# DaFunc.net
KiCad netlist of a schematic drawn in EAGLE
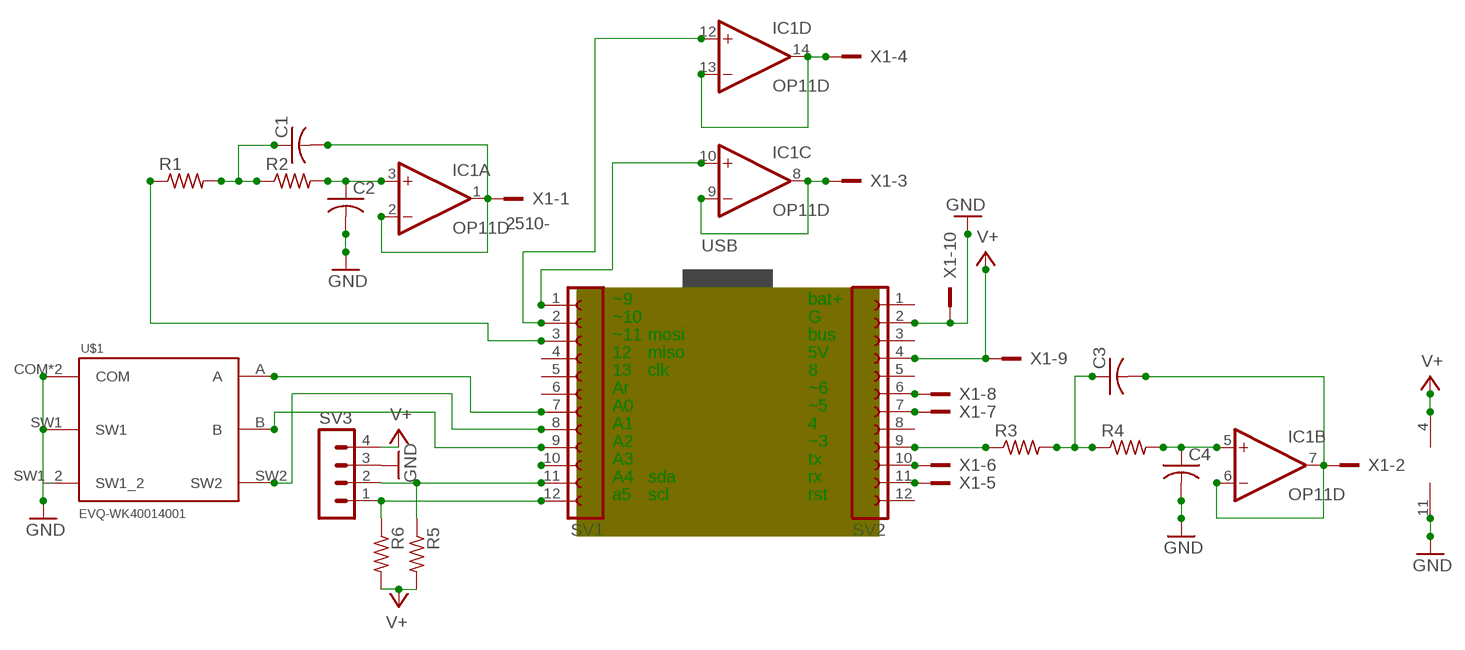
[diagram p0: schematic, sheet 1]

(export (version "E")
  (design (tool "Eeschema 10.0.6"))
  (components
    (comp (ref "C1")
      (value "C-USC0603")
      (footprint "eagle-import:C0603")
      (libsource (lib "eagle-import") (part "C-USC0603"))
    )
    (comp (ref "C2")
      (value "C-USC0603")
      (footprint "eagle-import:C0603")
      (libsource (lib "eagle-import") (part "C-USC0603"))
    )
    (comp (ref "C3")
      (value "C-USC0603")
      (footprint "eagle-import:C0603")
      (libsource (lib "eagle-import") (part "C-USC0603"))
    )
    (comp (ref "C4")
      (value "C-USC0603")
      (footprint "eagle-import:C0603")
      (libsource (lib "eagle-import") (part "C-USC0603"))
    )
    (comp (ref "IC1")
      (value "OP11D")
      (footprint "eagle-import:SO14")
      (libsource (lib "eagle-import") (part "OP11D"))
    )
    (comp (ref "R1")
      (value "R-US_R0603")
      (footprint "eagle-import:R0603")
      (libsource (lib "eagle-import") (part "R-US_R0603"))
    )
    (comp (ref "R2")
      (value "R-US_R0603")
      (footprint "eagle-import:R0603")
      (libsource (lib "eagle-import") (part "R-US_R0603"))
    )
    (comp (ref "R3")
      (value "R-US_R0603")
      (footprint "eagle-import:R0603")
      (libsource (lib "eagle-import") (part "R-US_R0603"))
    )
    (comp (ref "R4")
      (value "R-US_R0603")
      (footprint "eagle-import:R0603")
      (libsource (lib "eagle-import") (part "R-US_R0603"))
    )
    (comp (ref "R5")
      (value "R-US_R0603")
      (footprint "eagle-import:R0603")
      (libsource (lib "eagle-import") (part "R-US_R0603"))
    )
    (comp (ref "R6")
      (value "R-US_R0603")
      (footprint "eagle-import:R0603")
      (libsource (lib "eagle-import") (part "R-US_R0603"))
    )
    (comp (ref "SV1")
      (value "FE12-1")
      (footprint "eagle-import:FE12")
      (libsource (lib "eagle-import") (part "FE12-1"))
    )
    (comp (ref "SV2")
      (value "FE12-1")
      (footprint "eagle-import:FE12")
      (libsource (lib "eagle-import") (part "FE12-1"))
    )
    (comp (ref "SV3")
      (value "MA04-1")
      (footprint "eagle-import:MA04-1")
      (libsource (lib "eagle-import") (part "MA04-1"))
    )
    (comp (ref "U$1")
      (value "EVQ-WK40014001")
      (footprint "eagle-import:WK4")
      (libsource (lib "eagle-import") (part "EVQ-WK40014001"))
    )
    (comp (ref "X1")
      (value "2510-")
      (footprint "eagle-import:PAK100_2500-10")
      (fields (field (name "MF") "3M") (field (name "MPN") "2510-6002UB"))
      (libsource (lib "eagle-import") (part "2510-"))
    )
  )
  (nets
    (net (code "1") (name "GND") (class "Default")
      (node (ref "C2") (pin "2") (pinfunction "2_2") (pintype "passive"))
      (node (ref "C4") (pin "2") (pinfunction "2_2") (pintype "passive"))
      (node (ref "IC1") (pin "11") (pinfunction "V-_11") (pintype "power_in"))
      (node (ref "SV2") (pin "2") (pinfunction "2_2") (pintype "passive"))
      (node (ref "SV3") (pin "3") (pinfunction "3_3") (pintype "passive"))
      (node (ref "U$1") (pin "COM") (pinfunction "COM_COM") (pintype "bidirectional"))
      (node (ref "U$1") (pin "GND") (pinfunction "COM_GND") (pintype "bidirectional"))
      (node (ref "U$1") (pin "SW1") (pinfunction "SW1_SW1") (pintype "bidirectional"))
      (node (ref "U$1") (pin "SW1_2") (pinfunction "SW1_2_SW1_2") (pintype "bidirectional"))
      (node (ref "X1") (pin "10") (pinfunction "KL_10") (pintype "passive"))
    )
    (net (code "2") (name "Net-(C1-Pad1)") (class "Default")
      (node (ref "C1") (pin "1") (pinfunction "1_1") (pintype "passive"))
      (node (ref "R1") (pin "2") (pinfunction "2_2") (pintype "passive"))
      (node (ref "R2") (pin "1") (pinfunction "1_1") (pintype "passive"))
    )
    (net (code "3") (name "Net-(C3-Pad1)") (class "Default")
      (node (ref "C3") (pin "1") (pinfunction "1_1") (pintype "passive"))
      (node (ref "R3") (pin "2") (pinfunction "2_2") (pintype "passive"))
      (node (ref "R4") (pin "1") (pinfunction "1_1") (pintype "passive"))
    )
    (net (code "4") (name "Net-(IC1A-+IN)") (class "Default")
      (node (ref "C2") (pin "1") (pinfunction "1_1") (pintype "passive"))
      (node (ref "IC1") (pin "3") (pinfunction "+IN_3") (pintype "input"))
      (node (ref "R2") (pin "2") (pinfunction "2_2") (pintype "passive"))
    )
    (net (code "5") (name "Net-(IC1A--IN)") (class "Default")
      (node (ref "C1") (pin "2") (pinfunction "2_2") (pintype "passive"))
      (node (ref "IC1") (pin "1") (pinfunction "OUT_1") (pintype "output"))
      (node (ref "IC1") (pin "2") (pinfunction "-IN_2") (pintype "input"))
      (node (ref "X1") (pin "1") (pinfunction "KL_1") (pintype "passive"))
    )
    (net (code "6") (name "Net-(IC1B-+IN)") (class "Default")
      (node (ref "C4") (pin "1") (pinfunction "1_1") (pintype "passive"))
      (node (ref "IC1") (pin "5") (pinfunction "+IN_5") (pintype "input"))
      (node (ref "R4") (pin "2") (pinfunction "2_2") (pintype "passive"))
    )
    (net (code "7") (name "Net-(IC1B--IN)") (class "Default")
      (node (ref "C3") (pin "2") (pinfunction "2_2") (pintype "passive"))
      (node (ref "IC1") (pin "6") (pinfunction "-IN_6") (pintype "input"))
      (node (ref "IC1") (pin "7") (pinfunction "OUT_7") (pintype "output"))
      (node (ref "X1") (pin "2") (pinfunction "KL_2") (pintype "passive"))
    )
    (net (code "8") (name "Net-(IC1C-+IN)") (class "Default")
      (node (ref "IC1") (pin "10") (pinfunction "+IN_10") (pintype "input"))
      (node (ref "SV1") (pin "1") (pinfunction "1_1") (pintype "passive"))
    )
    (net (code "9") (name "Net-(IC1C--IN)") (class "Default")
      (node (ref "IC1") (pin "8") (pinfunction "OUT_8") (pintype "output"))
      (node (ref "IC1") (pin "9") (pinfunction "-IN_9") (pintype "input"))
      (node (ref "X1") (pin "3") (pinfunction "KL_3") (pintype "passive"))
    )
    (net (code "10") (name "Net-(IC1D-+IN)") (class "Default")
      (node (ref "IC1") (pin "12") (pinfunction "+IN_12") (pintype "input"))
      (node (ref "SV1") (pin "2") (pinfunction "2_2") (pintype "passive"))
    )
    (net (code "11") (name "Net-(IC1D--IN)") (class "Default")
      (node (ref "IC1") (pin "13") (pinfunction "-IN_13") (pintype "input"))
      (node (ref "IC1") (pin "14") (pinfunction "OUT_14") (pintype "output"))
      (node (ref "X1") (pin "4") (pinfunction "KL_4") (pintype "passive"))
    )
    (net (code "12") (name "Net-(R1-Pad1)") (class "Default")
      (node (ref "R1") (pin "1") (pinfunction "1_1") (pintype "passive"))
      (node (ref "SV1") (pin "3") (pinfunction "3_3") (pintype "passive"))
    )
    (net (code "13") (name "Net-(R3-Pad1)") (class "Default")
      (node (ref "R3") (pin "1") (pinfunction "1_1") (pintype "passive"))
      (node (ref "SV2") (pin "9") (pinfunction "9_9") (pintype "passive"))
    )
    (net (code "14") (name "Net-(R5-Pad1)") (class "Default")
      (node (ref "R5") (pin "1") (pinfunction "1_1") (pintype "passive"))
      (node (ref "SV1") (pin "11") (pinfunction "11_11") (pintype "passive"))
      (node (ref "SV3") (pin "2") (pinfunction "2_2") (pintype "passive"))
    )
    (net (code "15") (name "Net-(R6-Pad1)") (class "Default")
      (node (ref "R6") (pin "1") (pinfunction "1_1") (pintype "passive"))
      (node (ref "SV1") (pin "12") (pinfunction "12_12") (pintype "passive"))
      (node (ref "SV3") (pin "1") (pinfunction "1_1") (pintype "passive"))
    )
    (net (code "16") (name "Net-(SV1-Pad7)") (class "Default")
      (node (ref "SV1") (pin "7") (pinfunction "7_7") (pintype "passive"))
      (node (ref "U$1") (pin "A") (pinfunction "A_A") (pintype "bidirectional"))
    )
    (net (code "17") (name "Net-(SV1-Pad8)") (class "Default")
      (node (ref "SV1") (pin "8") (pinfunction "8_8") (pintype "passive"))
      (node (ref "U$1") (pin "SW2") (pinfunction "SW2_SW2") (pintype "bidirectional"))
    )
    (net (code "18") (name "Net-(SV1-Pad9)") (class "Default")
      (node (ref "SV1") (pin "9") (pinfunction "9_9") (pintype "passive"))
      (node (ref "U$1") (pin "B") (pinfunction "B_B") (pintype "bidirectional"))
    )
    (net (code "19") (name "Net-(X1F-KL)") (class "Default")
      (node (ref "SV2") (pin "11") (pinfunction "11_11") (pintype "passive"))
      (node (ref "X1") (pin "5") (pinfunction "KL_5") (pintype "passive"))
    )
    (net (code "20") (name "Net-(X1G-KL)") (class "Default")
      (node (ref "SV2") (pin "10") (pinfunction "10_10") (pintype "passive"))
      (node (ref "X1") (pin "6") (pinfunction "KL_6") (pintype "passive"))
    )
    (net (code "21") (name "Net-(X1H-KL)") (class "Default")
      (node (ref "SV2") (pin "7") (pinfunction "7_7") (pintype "passive"))
      (node (ref "X1") (pin "7") (pinfunction "KL_7") (pintype "passive"))
    )
    (net (code "22") (name "Net-(X1I-KL)") (class "Default")
      (node (ref "SV2") (pin "6") (pinfunction "6_6") (pintype "passive"))
      (node (ref "X1") (pin "8") (pinfunction "KL_8") (pintype "passive"))
    )
    (net (code "23") (name "V+") (class "Default")
      (node (ref "IC1") (pin "4") (pinfunction "V+_4") (pintype "power_in"))
      (node (ref "R5") (pin "2") (pinfunction "2_2") (pintype "passive"))
      (node (ref "R6") (pin "2") (pinfunction "2_2") (pintype "passive"))
      (node (ref "SV2") (pin "4") (pinfunction "4_4") (pintype "passive"))
      (node (ref "SV3") (pin "4") (pinfunction "4_4") (pintype "passive"))
      (node (ref "X1") (pin "9") (pinfunction "KL_9") (pintype "passive"))
    )
    (net (code "24") (name "unconnected-(SV1-Pad4)") (class "Default")
      (node (ref "SV1") (pin "4") (pinfunction "4_4") (pintype "passive"))
    )
    (net (code "25") (name "unconnected-(SV1-Pad5)") (class "Default")
      (node (ref "SV1") (pin "5") (pinfunction "5_5") (pintype "passive"))
    )
    (net (code "26") (name "unconnected-(SV1-Pad6)") (class "Default")
      (node (ref "SV1") (pin "6") (pinfunction "6_6") (pintype "passive"))
    )
    (net (code "27") (name "unconnected-(SV1-Pad10)") (class "Default")
      (node (ref "SV1") (pin "10") (pinfunction "10_10") (pintype "passive"))
    )
    (net (code "28") (name "unconnected-(SV2-Pad1)") (class "Default")
      (node (ref "SV2") (pin "1") (pinfunction "1_1") (pintype "passive"))
    )
    (net (code "29") (name "unconnected-(SV2-Pad3)") (class "Default")
      (node (ref "SV2") (pin "3") (pinfunction "3_3") (pintype "passive"))
    )
    (net (code "30") (name "unconnected-(SV2-Pad5)") (class "Default")
      (node (ref "SV2") (pin "5") (pinfunction "5_5") (pintype "passive"))
    )
    (net (code "31") (name "unconnected-(SV2-Pad8)") (class "Default")
      (node (ref "SV2") (pin "8") (pinfunction "8_8") (pintype "passive"))
    )
    (net (code "32") (name "unconnected-(SV2-Pad12)") (class "Default")
      (node (ref "SV2") (pin "12") (pinfunction "12_12") (pintype "passive"))
    )
  )
)
